# Howland.net
KiCad netlist of a schematic drawn in Altium Designer
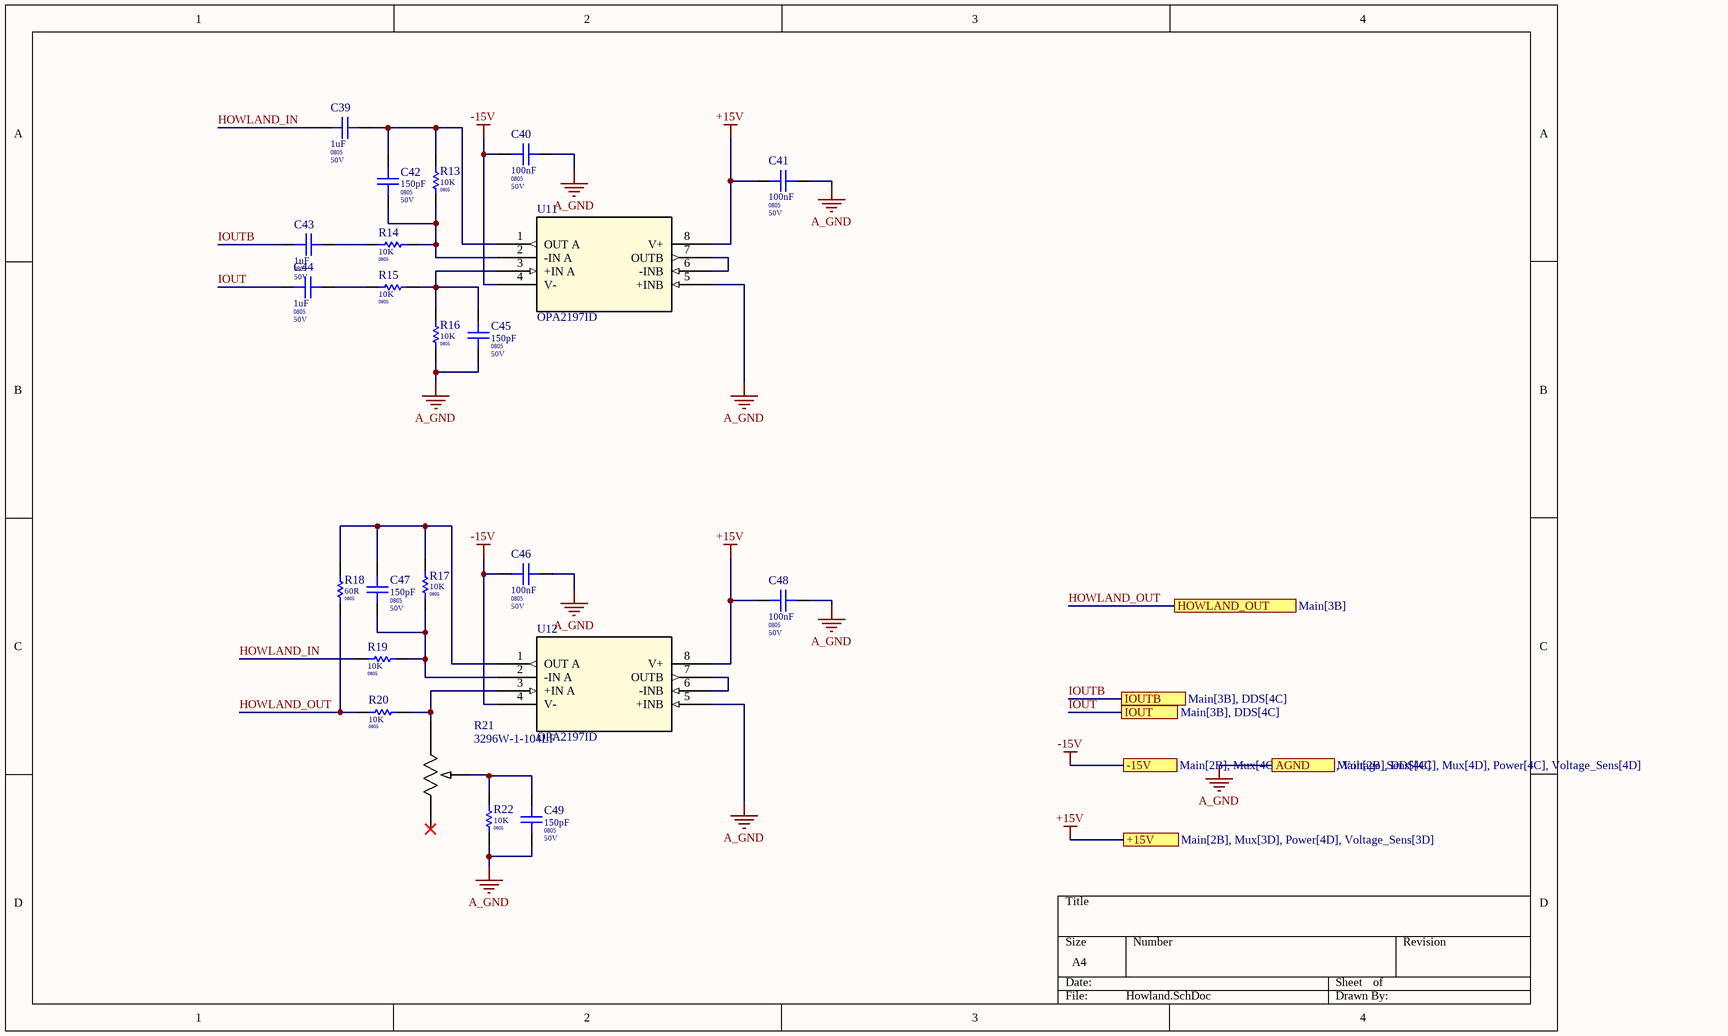
[diagram p0: Howland.SchDoc]

(export (version "E")
  (design (tool "Eeschema 10.0.6"))
  (components
    (comp (ref "C39")
      (value "1uF")
      (footprint "CAPC 0805")
      (description "Capacitor Ceramic 1uF 50V 0805")
      (fields
        (field (name "TOLERANCE") "%10")
        (field (name "PACKAGE / CASE") "0805")
        (field (name "VOLTAGE") "50V")
        (field (name "PART NUMBER") "CAPC0580")
      )
      (libsource (lib "Aesk Database Library") (part "NPCapacitor"))
    )
    (comp (ref "C40")
      (value "100nF")
      (footprint "CAPC 0805")
      (description "Capacitor Ceramic 100nF 50V 0805")
      (fields
        (field (name "TOLERANCE") "%10")
        (field (name "PACKAGE / CASE") "0805")
        (field (name "VOLTAGE") "50V")
        (field (name "PART NUMBER") "CAPC0572")
      )
      (libsource (lib "Aesk Database Library") (part "NPCapacitor"))
    )
    (comp (ref "C41")
      (value "100nF")
      (footprint "CAPC 0805")
      (description "Capacitor Ceramic 100nF 50V 0805")
      (fields
        (field (name "TOLERANCE") "%10")
        (field (name "PACKAGE / CASE") "0805")
        (field (name "VOLTAGE") "50V")
        (field (name "PART NUMBER") "CAPC0572")
      )
      (libsource (lib "Aesk Database Library") (part "NPCapacitor"))
    )
    (comp (ref "C42")
      (value "150pF")
      (footprint "CAPC 0805")
      (description "Capacitor Ceramic 150pF 50V 0805")
      (fields
        (field (name "TOLERANCE") "%10")
        (field (name "PACKAGE / CASE") "0805")
        (field (name "VOLTAGE") "50V")
        (field (name "PART NUMBER") "CAPC0549")
      )
      (libsource (lib "Aesk Database Library") (part "NPCapacitor"))
    )
    (comp (ref "C43")
      (value "1uF")
      (footprint "CAPC 0805")
      (description "Capacitor Ceramic 1uF 50V 0805")
      (fields
        (field (name "TOLERANCE") "%10")
        (field (name "PACKAGE / CASE") "0805")
        (field (name "VOLTAGE") "50V")
        (field (name "PART NUMBER") "CAPC0580")
      )
      (libsource (lib "Aesk Database Library") (part "NPCapacitor"))
    )
    (comp (ref "C44")
      (value "1uF")
      (footprint "CAPC 0805")
      (description "Capacitor Ceramic 1uF 50V 0805")
      (fields
        (field (name "TOLERANCE") "%10")
        (field (name "PACKAGE / CASE") "0805")
        (field (name "VOLTAGE") "50V")
        (field (name "PART NUMBER") "CAPC0580")
      )
      (libsource (lib "Aesk Database Library") (part "NPCapacitor"))
    )
    (comp (ref "C45")
      (value "150pF")
      (footprint "CAPC 0805")
      (description "Capacitor Ceramic 150pF 50V 0805")
      (fields
        (field (name "TOLERANCE") "%10")
        (field (name "PACKAGE / CASE") "0805")
        (field (name "VOLTAGE") "50V")
        (field (name "PART NUMBER") "CAPC0549")
      )
      (libsource (lib "Aesk Database Library") (part "NPCapacitor"))
    )
    (comp (ref "C46")
      (value "100nF")
      (footprint "CAPC 0805")
      (description "Capacitor Ceramic 100nF 50V 0805")
      (fields
        (field (name "TOLERANCE") "%10")
        (field (name "PACKAGE / CASE") "0805")
        (field (name "VOLTAGE") "50V")
        (field (name "PART NUMBER") "CAPC0572")
      )
      (libsource (lib "Aesk Database Library") (part "NPCapacitor"))
    )
    (comp (ref "C47")
      (value "150pF")
      (footprint "CAPC 0805")
      (description "Capacitor Ceramic 150pF 50V 0805")
      (fields
        (field (name "TOLERANCE") "%10")
        (field (name "PACKAGE / CASE") "0805")
        (field (name "VOLTAGE") "50V")
        (field (name "PART NUMBER") "CAPC0549")
      )
      (libsource (lib "Aesk Database Library") (part "NPCapacitor"))
    )
    (comp (ref "C48")
      (value "100nF")
      (footprint "CAPC 0805")
      (description "Capacitor Ceramic 100nF 50V 0805")
      (fields
        (field (name "TOLERANCE") "%10")
        (field (name "PACKAGE / CASE") "0805")
        (field (name "VOLTAGE") "50V")
        (field (name "PART NUMBER") "CAPC0572")
      )
      (libsource (lib "Aesk Database Library") (part "NPCapacitor"))
    )
    (comp (ref "C49")
      (value "150pF")
      (footprint "CAPC 0805")
      (description "Capacitor Ceramic 150pF 50V 0805")
      (fields
        (field (name "TOLERANCE") "%10")
        (field (name "PACKAGE / CASE") "0805")
        (field (name "VOLTAGE") "50V")
        (field (name "PART NUMBER") "CAPC0549")
      )
      (libsource (lib "Aesk Database Library") (part "NPCapacitor"))
    )
    (comp (ref "R13")
      (value "10K")
      (footprint "RESC 0805")
      (description "10K 0805")
      (fields
        (field (name "TOLERANCE") "%5")
        (field (name "POWER") "1/10W")
        (field (name "PACKAGE / CASE") "0805")
      )
      (libsource (lib "Aesk Database Library") (part "Resistor"))
    )
    (comp (ref "R14")
      (value "10K")
      (footprint "RESC 0805")
      (description "10K 0805")
      (fields
        (field (name "TOLERANCE") "%5")
        (field (name "POWER") "1/10W")
        (field (name "PACKAGE / CASE") "0805")
      )
      (libsource (lib "Aesk Database Library") (part "Resistor"))
    )
    (comp (ref "R15")
      (value "10K")
      (footprint "RESC 0805")
      (description "10K 0805")
      (fields
        (field (name "TOLERANCE") "%5")
        (field (name "POWER") "1/10W")
        (field (name "PACKAGE / CASE") "0805")
      )
      (libsource (lib "Aesk Database Library") (part "Resistor"))
    )
    (comp (ref "R16")
      (value "10K")
      (footprint "RESC 0805")
      (description "10K 0805")
      (fields
        (field (name "TOLERANCE") "%5")
        (field (name "POWER") "1/10W")
        (field (name "PACKAGE / CASE") "0805")
      )
      (libsource (lib "Aesk Database Library") (part "Resistor"))
    )
    (comp (ref "R17")
      (value "10K")
      (footprint "RESC 0805")
      (description "10K 0805")
      (fields
        (field (name "TOLERANCE") "%5")
        (field (name "POWER") "1/10W")
        (field (name "PACKAGE / CASE") "0805")
      )
      (libsource (lib "Aesk Database Library") (part "Resistor"))
    )
    (comp (ref "R18")
      (value "60R")
      (footprint "RESC 0805")
      (description "160R 0805")
      (fields
        (field (name "TOLERANCE") "%5")
        (field (name "POWER") "1/10W")
        (field (name "PACKAGE / CASE") "0805")
      )
      (libsource (lib "Aesk Database Library") (part "Resistor"))
    )
    (comp (ref "R19")
      (value "10K")
      (footprint "RESC 0805")
      (description "10K 0805")
      (fields
        (field (name "TOLERANCE") "%5")
        (field (name "POWER") "1/10W")
        (field (name "PACKAGE / CASE") "0805")
      )
      (libsource (lib "Aesk Database Library") (part "Resistor"))
    )
    (comp (ref "R20")
      (value "10K")
      (footprint "RESC 0805")
      (description "10K 0805")
      (fields
        (field (name "TOLERANCE") "%5")
        (field (name "POWER") "1/10W")
        (field (name "PACKAGE / CASE") "0805")
      )
      (libsource (lib "Aesk Database Library") (part "Resistor"))
    )
    (comp (ref "R21")
      (value "3296W-1-104LF")
      (footprint "POT_3296W")
      (description "Description")
      (fields (field (name "COPYRIGHT") "Copyright (C) 2025 Ultra Librarian. All rights reserved."))
      (libsource (lib "Schlib1") (part "3296W-1-104LF"))
    )
    (comp (ref "R22")
      (value "10K")
      (footprint "RESC 0805")
      (description "10K 0805")
      (fields
        (field (name "TOLERANCE") "%5")
        (field (name "POWER") "1/10W")
        (field (name "PACKAGE / CASE") "0805")
      )
      (libsource (lib "Aesk Database Library") (part "Resistor"))
    )
    (comp (ref "U11")
      (value "OPA2197ID")
      (footprint "D8_TEX-M")
      (description "Dual 36-V, precision, rail-to-rail input output, low offset voltage op amp 8-SOIC -40 to 125")
      (fields (field (name "COPYRIGHT") "Copyright (C) 2025 Ultra Librarian. All rights reserved."))
      (libsource (lib "Schlib1") (part "OPA2197ID"))
    )
    (comp (ref "U12")
      (value "OPA2197ID")
      (footprint "D8_TEX-M")
      (description "Dual 36-V, precision, rail-to-rail input output, low offset voltage op amp 8-SOIC -40 to 125")
      (fields (field (name "COPYRIGHT") "Copyright (C) 2025 Ultra Librarian. All rights reserved."))
      (libsource (lib "Schlib1") (part "OPA2197ID"))
    )
  )
  (nets
    (net (code "1") (name "+15V") (class "Default")
      (node (ref "C41") (pin "2") (pinfunction "2_2") (pintype "passive"))
      (node (ref "C48") (pin "2") (pinfunction "2_2") (pintype "passive"))
      (node (ref "U11") (pin "8") (pinfunction "V+_8") (pintype "power_in"))
      (node (ref "U12") (pin "8") (pinfunction "V+_8") (pintype "power_in"))
    )
    (net (code "2") (name "-15V") (class "Default")
      (node (ref "C40") (pin "2") (pinfunction "2_2") (pintype "passive"))
      (node (ref "C46") (pin "2") (pinfunction "2_2") (pintype "passive"))
      (node (ref "U11") (pin "4") (pinfunction "V-_4") (pintype "power_in"))
      (node (ref "U12") (pin "4") (pinfunction "V-_4") (pintype "power_in"))
    )
    (net (code "3") (name "/HOWLAND_IN") (class "Default")
      (node (ref "C39") (pin "1") (pinfunction "1_1") (pintype "passive"))
      (node (ref "R19") (pin "1") (pinfunction "1_1") (pintype "passive"))
    )
    (net (code "4") (name "/HOWLAND_OUT") (class "Default")
      (node (ref "R18") (pin "1") (pinfunction "1_1") (pintype "passive"))
      (node (ref "R20") (pin "1") (pinfunction "1_1") (pintype "passive"))
    )
    (net (code "5") (name "/IOUT") (class "Default")
      (node (ref "C44") (pin "1") (pinfunction "1_1") (pintype "passive"))
    )
    (net (code "6") (name "/IOUTB") (class "Default")
      (node (ref "C43") (pin "1") (pinfunction "1_1") (pintype "passive"))
    )
    (net (code "7") (name "A_GND") (class "Default")
      (node (ref "C40") (pin "1") (pinfunction "1_1") (pintype "passive"))
      (node (ref "C41") (pin "1") (pinfunction "1_1") (pintype "passive"))
      (node (ref "C45") (pin "1") (pinfunction "1_1") (pintype "passive"))
      (node (ref "C46") (pin "1") (pinfunction "1_1") (pintype "passive"))
      (node (ref "C48") (pin "1") (pinfunction "1_1") (pintype "passive"))
      (node (ref "C49") (pin "1") (pinfunction "1_1") (pintype "passive"))
      (node (ref "R16") (pin "2") (pinfunction "2_2") (pintype "passive"))
      (node (ref "R22") (pin "2") (pinfunction "2_2") (pintype "passive"))
      (node (ref "U11") (pin "5") (pinfunction "+INB_5") (pintype "input"))
      (node (ref "U12") (pin "5") (pinfunction "+INB_5") (pintype "input"))
    )
    (net (code "8") (name "Net-(C43-Pad2)") (class "Default")
      (node (ref "C43") (pin "2") (pinfunction "2_2") (pintype "passive"))
      (node (ref "R14") (pin "2") (pinfunction "2_2") (pintype "passive"))
    )
    (net (code "9") (name "Net-(C44-Pad2)") (class "Default")
      (node (ref "C44") (pin "2") (pinfunction "2_2") (pintype "passive"))
      (node (ref "R15") (pin "2") (pinfunction "2_2") (pintype "passive"))
    )
    (net (code "10") (name "Net-(C49-Pad2)") (class "Default")
      (node (ref "C49") (pin "2") (pinfunction "2_2") (pintype "passive"))
      (node (ref "R21") (pin "2") (pinfunction "2_2") (pintype "passive"))
      (node (ref "R22") (pin "1") (pinfunction "1_1") (pintype "passive"))
    )
    (net (code "11") (name "Net-(U11-+IN_A)") (class "Default")
      (node (ref "C45") (pin "2") (pinfunction "2_2") (pintype "passive"))
      (node (ref "R15") (pin "1") (pinfunction "1_1") (pintype "passive"))
      (node (ref "R16") (pin "1") (pinfunction "1_1") (pintype "passive"))
      (node (ref "U11") (pin "3") (pinfunction "+IN_A_3") (pintype "input"))
    )
    (net (code "12") (name "Net-(U11--INB)") (class "Default")
      (node (ref "U11") (pin "6") (pinfunction "-INB_6") (pintype "input"))
      (node (ref "U11") (pin "7") (pinfunction "OUTB_7") (pintype "output"))
    )
    (net (code "13") (name "Net-(U11--IN_A)") (class "Default")
      (node (ref "C42") (pin "1") (pinfunction "1_1") (pintype "passive"))
      (node (ref "R13") (pin "2") (pinfunction "2_2") (pintype "passive"))
      (node (ref "R14") (pin "1") (pinfunction "1_1") (pintype "passive"))
      (node (ref "U11") (pin "2") (pinfunction "-IN_A_2") (pintype "passive"))
    )
    (net (code "14") (name "Net-(U11-OUT_A)") (class "Default")
      (node (ref "C39") (pin "2") (pinfunction "2_2") (pintype "passive"))
      (node (ref "C42") (pin "2") (pinfunction "2_2") (pintype "passive"))
      (node (ref "R13") (pin "1") (pinfunction "1_1") (pintype "passive"))
      (node (ref "U11") (pin "1") (pinfunction "OUT_A_1") (pintype "output"))
    )
    (net (code "15") (name "Net-(U12-+IN_A)") (class "Default")
      (node (ref "R20") (pin "2") (pinfunction "2_2") (pintype "passive"))
      (node (ref "R21") (pin "1") (pinfunction "1_1") (pintype "passive"))
      (node (ref "U12") (pin "3") (pinfunction "+IN_A_3") (pintype "input"))
    )
    (net (code "16") (name "Net-(U12--INB)") (class "Default")
      (node (ref "U12") (pin "6") (pinfunction "-INB_6") (pintype "input"))
      (node (ref "U12") (pin "7") (pinfunction "OUTB_7") (pintype "output"))
    )
    (net (code "17") (name "Net-(U12--IN_A)") (class "Default")
      (node (ref "C47") (pin "1") (pinfunction "1_1") (pintype "passive"))
      (node (ref "R17") (pin "2") (pinfunction "2_2") (pintype "passive"))
      (node (ref "R19") (pin "2") (pinfunction "2_2") (pintype "passive"))
      (node (ref "U12") (pin "2") (pinfunction "-IN_A_2") (pintype "passive"))
    )
    (net (code "18") (name "Net-(U12-OUT_A)") (class "Default")
      (node (ref "C47") (pin "2") (pinfunction "2_2") (pintype "passive"))
      (node (ref "R17") (pin "1") (pinfunction "1_1") (pintype "passive"))
      (node (ref "R18") (pin "2") (pinfunction "2_2") (pintype "passive"))
      (node (ref "U12") (pin "1") (pinfunction "OUT_A_1") (pintype "output"))
    )
    (net (code "19") (name "unconnected-(R21-Pad3)") (class "Default")
      (node (ref "R21") (pin "3") (pinfunction "3_3") (pintype "passive+no_connect"))
    )
  )
)
